# dcs_measurements.net
KiCad netlist of a schematic drawn in EAGLE
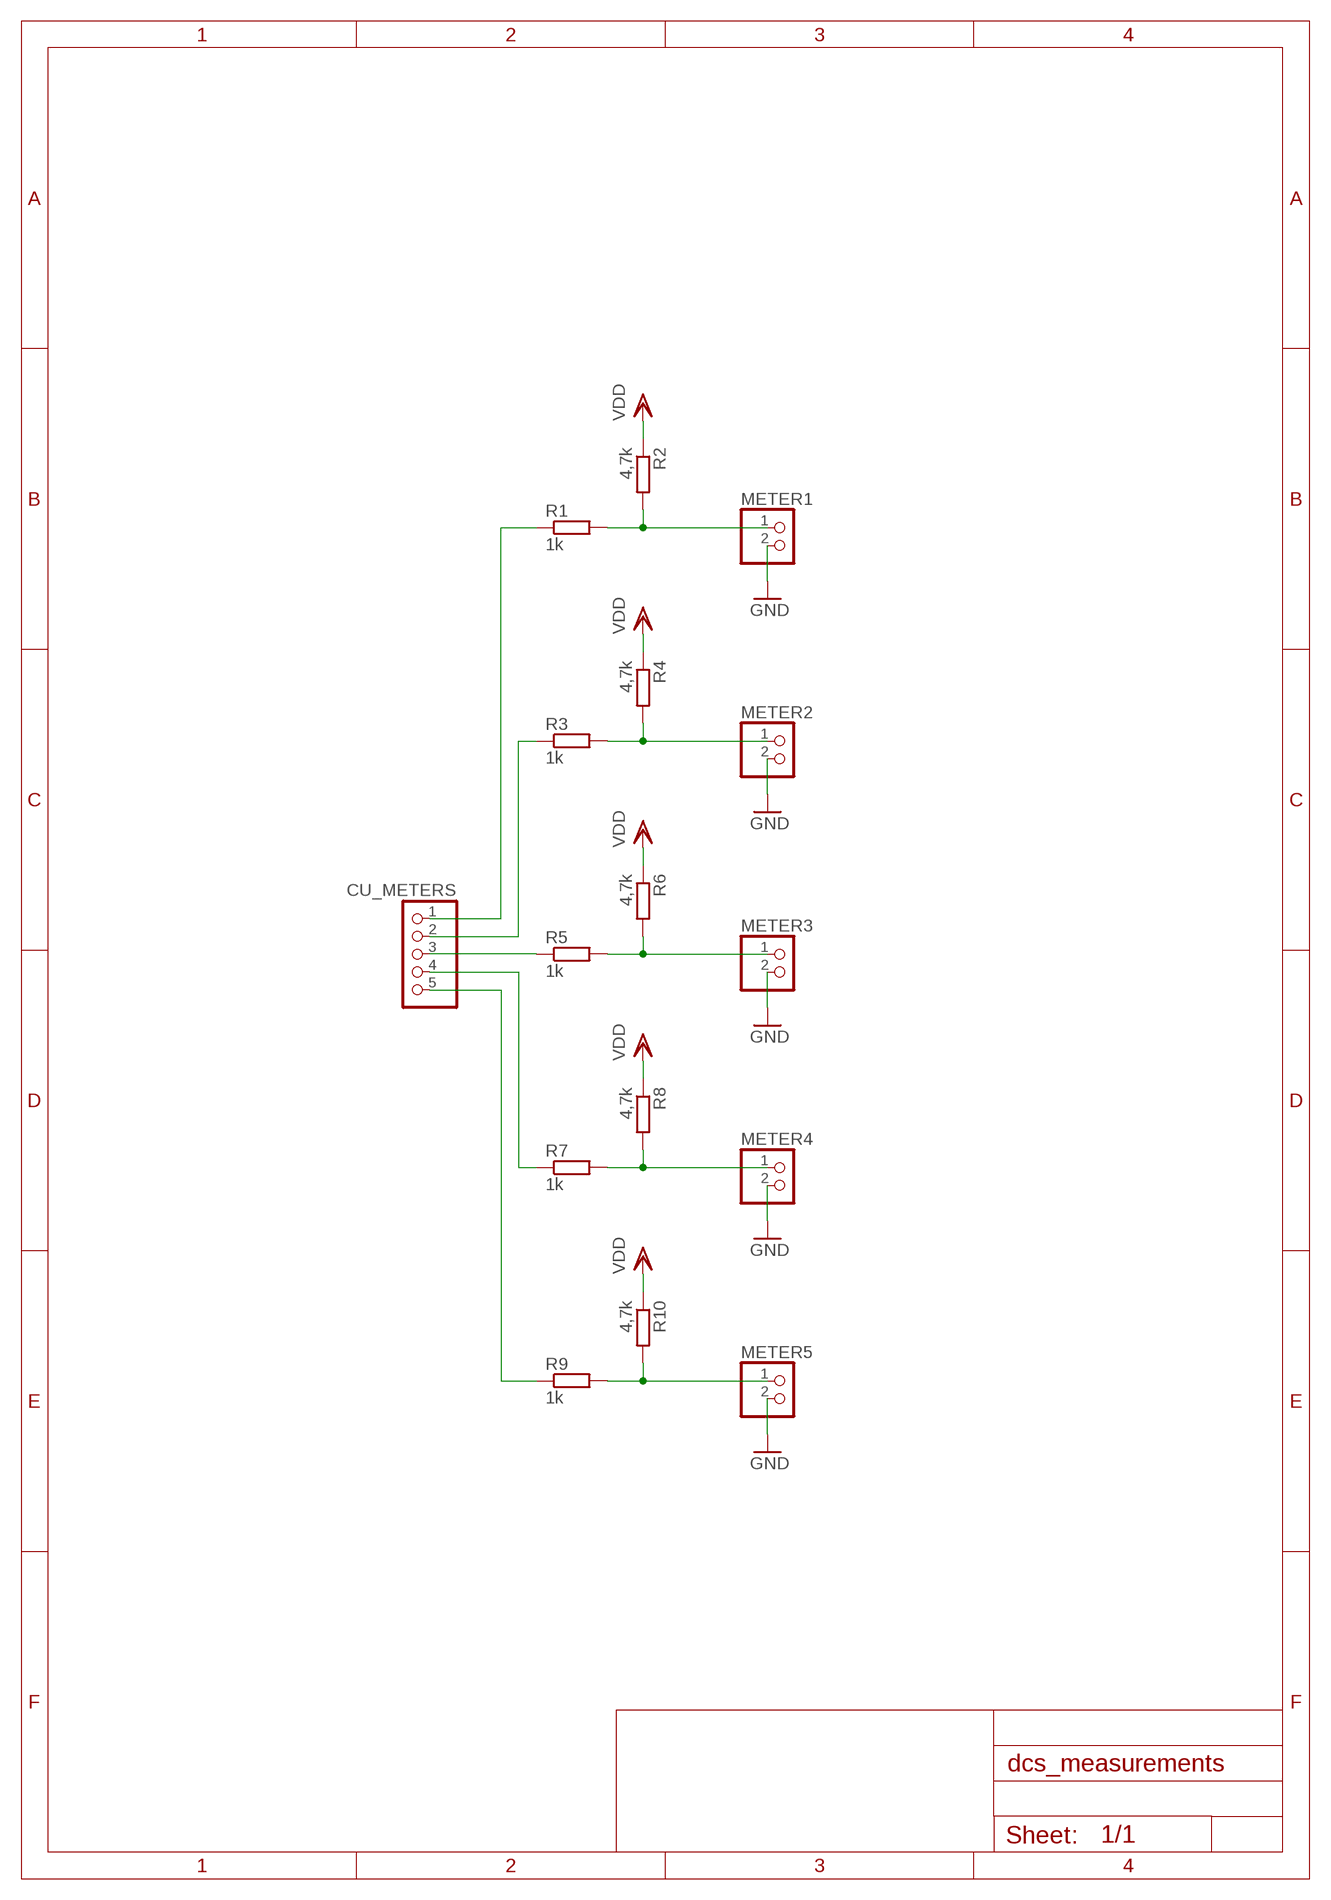
[diagram p0: schematic, sheet 1]

(export (version "E")
  (design (tool "Eeschema 10.0.6"))
  (components
    (comp (ref "CU_METERS")
      (value "PINHD-1X5")
      (footprint "eagle-import:1X05")
      (libsource (lib "eagle-import") (part "PINHD-1X5"))
    )
    (comp (ref "METER1")
      (value "PINHD-1X2")
      (footprint "eagle-import:1X02")
      (libsource (lib "eagle-import") (part "PINHD-1X2"))
    )
    (comp (ref "METER2")
      (value "PINHD-1X2")
      (footprint "eagle-import:1X02")
      (libsource (lib "eagle-import") (part "PINHD-1X2"))
    )
    (comp (ref "METER3")
      (value "PINHD-1X2")
      (footprint "eagle-import:1X02")
      (libsource (lib "eagle-import") (part "PINHD-1X2"))
    )
    (comp (ref "METER4")
      (value "PINHD-1X2")
      (footprint "eagle-import:1X02")
      (libsource (lib "eagle-import") (part "PINHD-1X2"))
    )
    (comp (ref "METER5")
      (value "PINHD-1X2")
      (footprint "eagle-import:1X02")
      (libsource (lib "eagle-import") (part "PINHD-1X2"))
    )
    (comp (ref "R1")
      (value "1k")
      (footprint "eagle-import:0207_7")
      (libsource (lib "eagle-import") (part "R-EU_0207/7"))
    )
    (comp (ref "R2")
      (value "4,7k")
      (footprint "eagle-import:0207_7")
      (libsource (lib "eagle-import") (part "R-EU_0207/7"))
    )
    (comp (ref "R3")
      (value "1k")
      (footprint "eagle-import:0207_7")
      (libsource (lib "eagle-import") (part "R-EU_0207/7"))
    )
    (comp (ref "R4")
      (value "4,7k")
      (footprint "eagle-import:0207_7")
      (libsource (lib "eagle-import") (part "R-EU_0207/7"))
    )
    (comp (ref "R5")
      (value "1k")
      (footprint "eagle-import:0207_7")
      (libsource (lib "eagle-import") (part "R-EU_0207/7"))
    )
    (comp (ref "R6")
      (value "4,7k")
      (footprint "eagle-import:0207_7")
      (libsource (lib "eagle-import") (part "R-EU_0207/7"))
    )
    (comp (ref "R7")
      (value "1k")
      (footprint "eagle-import:0207_7")
      (libsource (lib "eagle-import") (part "R-EU_0207/7"))
    )
    (comp (ref "R8")
      (value "4,7k")
      (footprint "eagle-import:0207_7")
      (libsource (lib "eagle-import") (part "R-EU_0207/7"))
    )
    (comp (ref "R9")
      (value "1k")
      (footprint "eagle-import:0207_7")
      (libsource (lib "eagle-import") (part "R-EU_0207/7"))
    )
    (comp (ref "R10")
      (value "4,7k")
      (footprint "eagle-import:0207_7")
      (libsource (lib "eagle-import") (part "R-EU_0207/7"))
    )
  )
  (nets
    (net (code "1") (name "GND") (class "Default")
      (node (ref "METER1") (pin "2") (pinfunction "2_2") (pintype "passive"))
      (node (ref "METER2") (pin "2") (pinfunction "2_2") (pintype "passive"))
      (node (ref "METER3") (pin "2") (pinfunction "2_2") (pintype "passive"))
      (node (ref "METER4") (pin "2") (pinfunction "2_2") (pintype "passive"))
      (node (ref "METER5") (pin "2") (pinfunction "2_2") (pintype "passive"))
    )
    (net (code "2") (name "Net-(CU_METERS-Pad1)") (class "Default")
      (node (ref "CU_METERS") (pin "1") (pinfunction "1_1") (pintype "passive"))
      (node (ref "R1") (pin "1") (pinfunction "1_1") (pintype "passive"))
    )
    (net (code "3") (name "Net-(CU_METERS-Pad2)") (class "Default")
      (node (ref "CU_METERS") (pin "2") (pinfunction "2_2") (pintype "passive"))
      (node (ref "R3") (pin "1") (pinfunction "1_1") (pintype "passive"))
    )
    (net (code "4") (name "Net-(CU_METERS-Pad3)") (class "Default")
      (node (ref "CU_METERS") (pin "3") (pinfunction "3_3") (pintype "passive"))
      (node (ref "R5") (pin "1") (pinfunction "1_1") (pintype "passive"))
    )
    (net (code "5") (name "Net-(CU_METERS-Pad4)") (class "Default")
      (node (ref "CU_METERS") (pin "4") (pinfunction "4_4") (pintype "passive"))
      (node (ref "R7") (pin "1") (pinfunction "1_1") (pintype "passive"))
    )
    (net (code "6") (name "Net-(CU_METERS-Pad5)") (class "Default")
      (node (ref "CU_METERS") (pin "5") (pinfunction "5_5") (pintype "passive"))
      (node (ref "R9") (pin "1") (pinfunction "1_1") (pintype "passive"))
    )
    (net (code "7") (name "Net-(METER1-Pad1)") (class "Default")
      (node (ref "METER1") (pin "1") (pinfunction "1_1") (pintype "passive"))
      (node (ref "R1") (pin "2") (pinfunction "2_2") (pintype "passive"))
      (node (ref "R2") (pin "2") (pinfunction "2_2") (pintype "passive"))
    )
    (net (code "8") (name "Net-(METER2-Pad1)") (class "Default")
      (node (ref "METER2") (pin "1") (pinfunction "1_1") (pintype "passive"))
      (node (ref "R3") (pin "2") (pinfunction "2_2") (pintype "passive"))
      (node (ref "R4") (pin "2") (pinfunction "2_2") (pintype "passive"))
    )
    (net (code "9") (name "Net-(METER3-Pad1)") (class "Default")
      (node (ref "METER3") (pin "1") (pinfunction "1_1") (pintype "passive"))
      (node (ref "R5") (pin "2") (pinfunction "2_2") (pintype "passive"))
      (node (ref "R6") (pin "2") (pinfunction "2_2") (pintype "passive"))
    )
    (net (code "10") (name "Net-(METER4-Pad1)") (class "Default")
      (node (ref "METER4") (pin "1") (pinfunction "1_1") (pintype "passive"))
      (node (ref "R7") (pin "2") (pinfunction "2_2") (pintype "passive"))
      (node (ref "R8") (pin "2") (pinfunction "2_2") (pintype "passive"))
    )
    (net (code "11") (name "Net-(METER5-Pad1)") (class "Default")
      (node (ref "METER5") (pin "1") (pinfunction "1_1") (pintype "passive"))
      (node (ref "R10") (pin "2") (pinfunction "2_2") (pintype "passive"))
      (node (ref "R9") (pin "2") (pinfunction "2_2") (pintype "passive"))
    )
    (net (code "12") (name "VDD") (class "Default")
      (node (ref "R10") (pin "1") (pinfunction "1_1") (pintype "passive"))
      (node (ref "R2") (pin "1") (pinfunction "1_1") (pintype "passive"))
      (node (ref "R4") (pin "1") (pinfunction "1_1") (pintype "passive"))
      (node (ref "R6") (pin "1") (pinfunction "1_1") (pintype "passive"))
      (node (ref "R8") (pin "1") (pinfunction "1_1") (pintype "passive"))
    )
  )
)
